# 3pinDXL-data.net
KiCad netlist of a schematic drawn in EAGLE
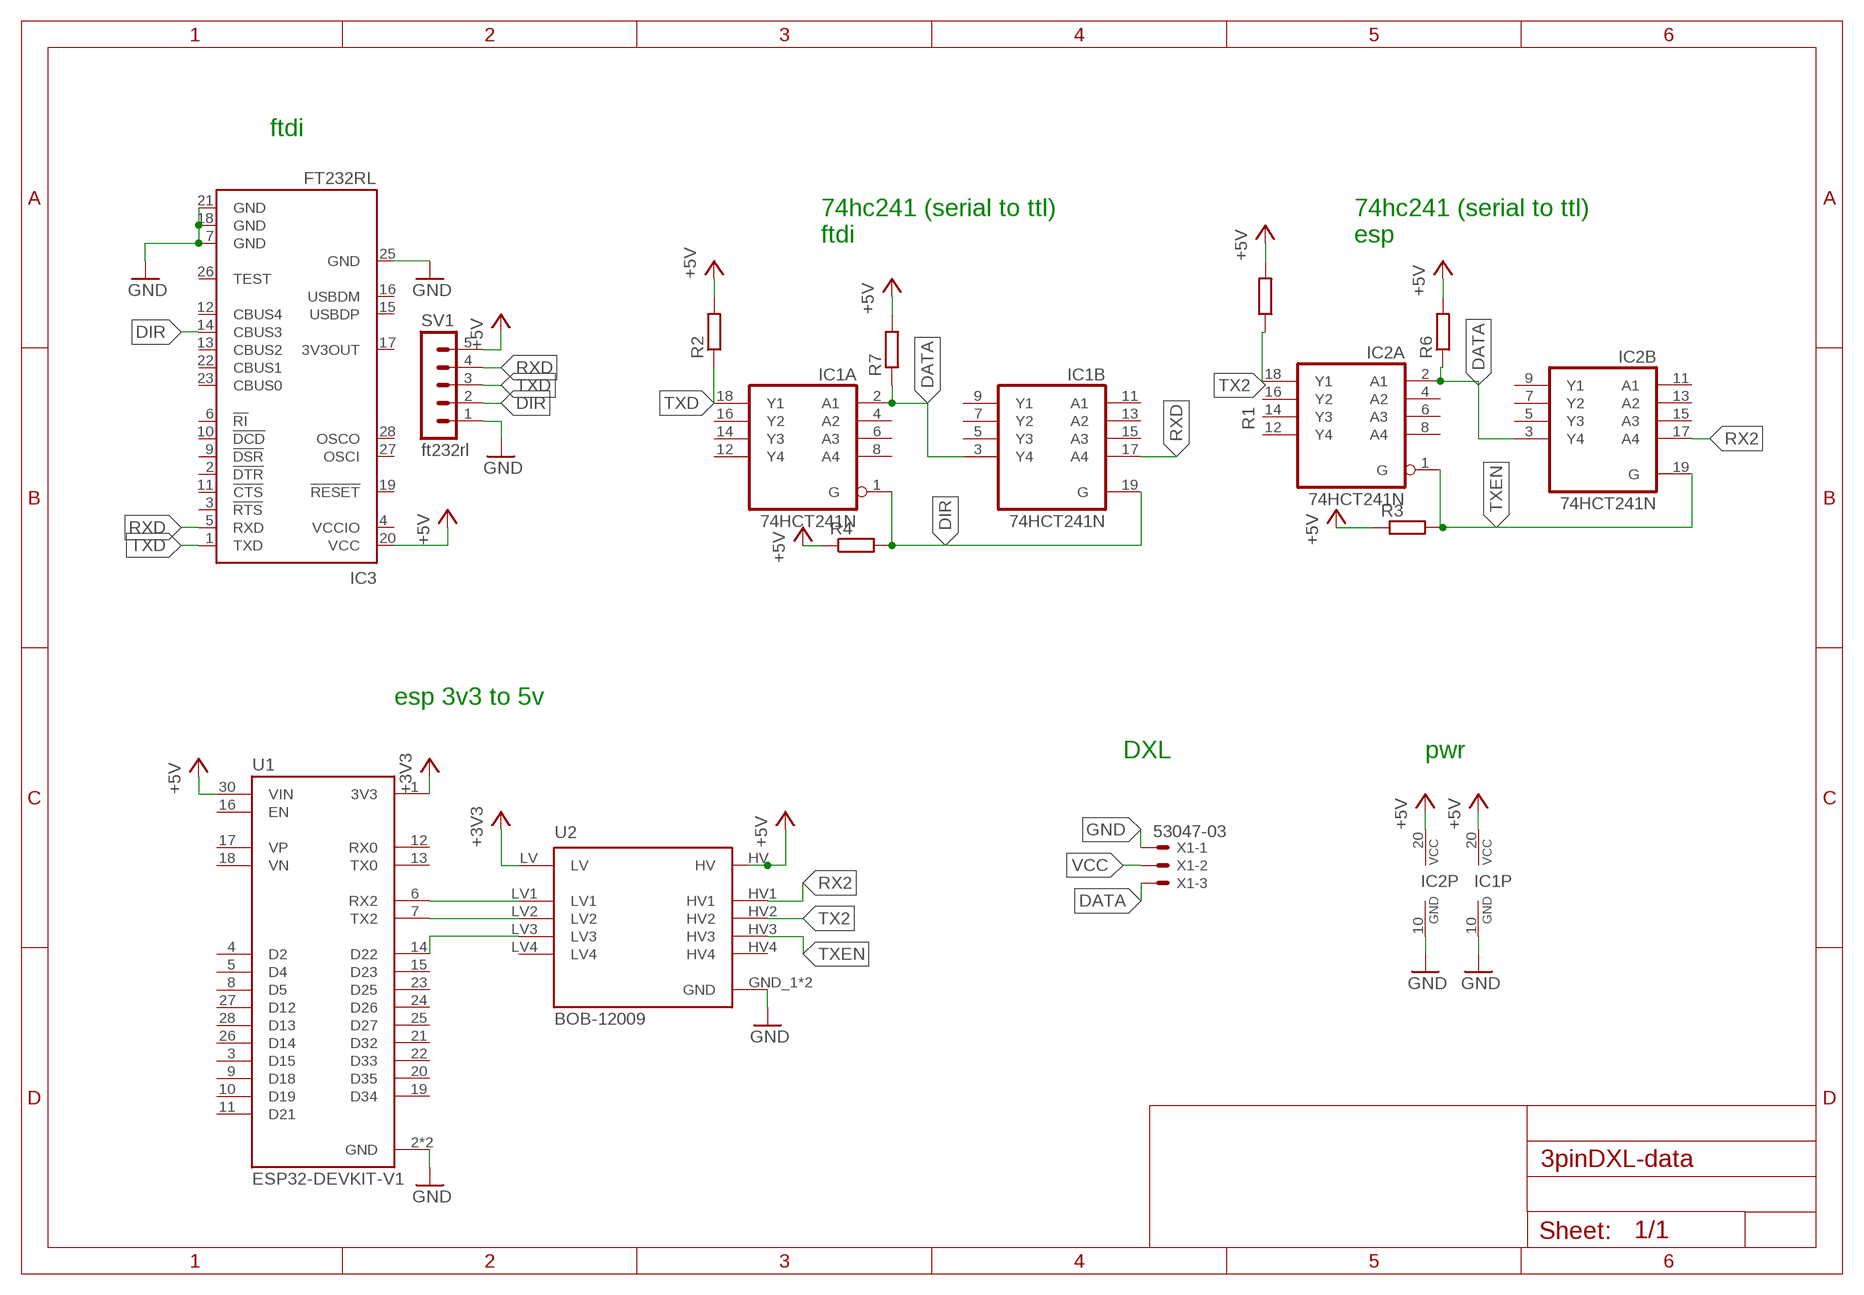
[diagram p0: schematic, sheet 1]

(export (version "E")
  (design (tool "Eeschema 10.0.6"))
  (components
    (comp (ref "IC1")
      (value "74HCT241N")
      (footprint "eagle-import:DIL20")
      (libsource (lib "eagle-import") (part "74241NHCT"))
    )
    (comp (ref "IC2")
      (value "74HCT241N")
      (footprint "eagle-import:DIL20")
      (libsource (lib "eagle-import") (part "74241NHCT"))
    )
    (comp (ref "IC3")
      (value "FT232RL")
      (footprint "eagle-import:SSOP28")
      (libsource (lib "eagle-import") (part "FT232RL"))
    )
    (comp (ref "R1")
      (value "R-EU_R0805")
      (footprint "eagle-import:R0805")
      (libsource (lib "eagle-import") (part "R-EU_R0805"))
    )
    (comp (ref "R2")
      (value "R-EU_R0805")
      (footprint "eagle-import:R0805")
      (libsource (lib "eagle-import") (part "R-EU_R0805"))
    )
    (comp (ref "R3")
      (value "R-EU_R0805")
      (footprint "eagle-import:R0805")
      (libsource (lib "eagle-import") (part "R-EU_R0805"))
    )
    (comp (ref "R4")
      (value "R-EU_R0805")
      (footprint "eagle-import:R0805")
      (libsource (lib "eagle-import") (part "R-EU_R0805"))
    )
    (comp (ref "R6")
      (value "R-EU_R0805")
      (footprint "eagle-import:R0805")
      (libsource (lib "eagle-import") (part "R-EU_R0805"))
    )
    (comp (ref "R7")
      (value "R-EU_R0805")
      (footprint "eagle-import:R0805")
      (libsource (lib "eagle-import") (part "R-EU_R0805"))
    )
    (comp (ref "SV1")
      (value "ft232rl")
      (footprint "eagle-import:MA05-1")
      (libsource (lib "eagle-import") (part "MA05-1"))
    )
    (comp (ref "U1")
      (value "ESP32-DEVKIT-V1")
      (footprint "eagle-import:MODULE_ESP32_DEVKIT_V1")
      (fields (field (name "MF") "Do it"))
      (libsource (lib "eagle-import") (part "ESP32-DEVKIT-V1"))
    )
    (comp (ref "U2")
      (value "BOB-12009")
      (footprint "eagle-import:CONV_BOB-12009")
      (fields (field (name "MF") "SparkFun"))
      (libsource (lib "eagle-import") (part "BOB-12009"))
    )
    (comp (ref "X1")
      (value "53047-03")
      (footprint "eagle-import:53047-03")
      (fields (field (name "MF") "MOLEX") (field (name "MPN") "530470310"))
      (libsource (lib "eagle-import") (part "53?-03047"))
    )
  )
  (nets
    (net (code "1") (name "+3V3") (class "Default")
      (node (ref "U1") (pin "1") (pinfunction "3V3_1") (pintype "output"))
      (node (ref "U2") (pin "LV") (pinfunction "LV_LV") (pintype "bidirectional"))
    )
    (net (code "2") (name "+5V") (class "Default")
      (node (ref "IC1") (pin "20") (pinfunction "VCC_20") (pintype "power_in"))
      (node (ref "IC2") (pin "20") (pinfunction "VCC_20") (pintype "power_in"))
      (node (ref "IC3") (pin "20") (pinfunction "VCC_20") (pintype "power_in"))
      (node (ref "R1") (pin "2") (pinfunction "2_2") (pintype "passive"))
      (node (ref "R2") (pin "2") (pinfunction "2_2") (pintype "passive"))
      (node (ref "R3") (pin "1") (pinfunction "1_1") (pintype "passive"))
      (node (ref "R4") (pin "1") (pinfunction "1_1") (pintype "passive"))
      (node (ref "R6") (pin "2") (pinfunction "2_2") (pintype "passive"))
      (node (ref "R7") (pin "2") (pinfunction "2_2") (pintype "passive"))
      (node (ref "SV1") (pin "5") (pinfunction "5_5") (pintype "passive"))
      (node (ref "U1") (pin "30") (pinfunction "VIN_30") (pintype "input"))
      (node (ref "U2") (pin "HV") (pinfunction "HV_HV") (pintype "bidirectional"))
    )
    (net (code "3") (name "/VCCIO") (class "Default")
      (node (ref "IC3") (pin "4") (pinfunction "VCCIO_4") (pintype "power_in"))
    )
    (net (code "4") (name "DATA") (class "Default")
      (node (ref "IC1") (pin "2") (pinfunction "A1_2") (pintype "input"))
      (node (ref "IC1") (pin "3") (pinfunction "Y4_3") (pintype "tri_state"))
      (node (ref "IC2") (pin "2") (pinfunction "A1_2") (pintype "input"))
      (node (ref "IC2") (pin "3") (pinfunction "Y4_3") (pintype "tri_state"))
      (node (ref "R6") (pin "1") (pinfunction "1_1") (pintype "passive"))
      (node (ref "R7") (pin "1") (pinfunction "1_1") (pintype "passive"))
      (node (ref "X1") (pin "3") (pinfunction "S_3") (pintype "passive"))
    )
    (net (code "5") (name "DIR") (class "Default")
      (node (ref "IC1") (pin "1") (pinfunction "G_1") (pintype "input"))
      (node (ref "IC1") (pin "19") (pinfunction "G_19") (pintype "input"))
      (node (ref "IC3") (pin "14") (pinfunction "CBUS3_14") (pintype "bidirectional"))
      (node (ref "R4") (pin "2") (pinfunction "2_2") (pintype "passive"))
      (node (ref "SV1") (pin "2") (pinfunction "2_2") (pintype "passive"))
    )
    (net (code "6") (name "GND") (class "Default")
      (node (ref "IC1") (pin "10") (pinfunction "GND_10") (pintype "power_in"))
      (node (ref "IC2") (pin "10") (pinfunction "GND_10") (pintype "power_in"))
      (node (ref "IC3") (pin "18") (pinfunction "GND_18") (pintype "power_in"))
      (node (ref "IC3") (pin "21") (pinfunction "GND_21") (pintype "power_in"))
      (node (ref "IC3") (pin "25") (pinfunction "GND_25") (pintype "power_in"))
      (node (ref "IC3") (pin "7") (pinfunction "GND_7") (pintype "power_in"))
      (node (ref "SV1") (pin "1") (pinfunction "1_1") (pintype "passive"))
      (node (ref "U1") (pin "2") (pinfunction "GND_2") (pintype "power_in"))
      (node (ref "U1") (pin "29") (pinfunction "GND_29") (pintype "power_in"))
      (node (ref "U2") (pin "GND_1") (pinfunction "GND_GND_1") (pintype "power_in"))
      (node (ref "U2") (pin "GND_2") (pinfunction "GND_GND_2") (pintype "power_in"))
      (node (ref "X1") (pin "1") (pinfunction "S_1") (pintype "passive"))
    )
    (net (code "7") (name "Net-(U1-D22)") (class "Default")
      (node (ref "U1") (pin "14") (pinfunction "D22_14") (pintype "bidirectional"))
      (node (ref "U2") (pin "LV3") (pinfunction "LV3_LV3") (pintype "bidirectional"))
    )
    (net (code "8") (name "Net-(U1-RX2)") (class "Default")
      (node (ref "U1") (pin "6") (pinfunction "RX2_6") (pintype "input"))
      (node (ref "U2") (pin "LV1") (pinfunction "LV1_LV1") (pintype "bidirectional"))
    )
    (net (code "9") (name "Net-(U1-TX2)") (class "Default")
      (node (ref "U1") (pin "7") (pinfunction "TX2_7") (pintype "output"))
      (node (ref "U2") (pin "LV2") (pinfunction "LV2_LV2") (pintype "bidirectional"))
    )
    (net (code "10") (name "RX2") (class "Default")
      (node (ref "IC2") (pin "17") (pinfunction "A4_17") (pintype "input"))
      (node (ref "U2") (pin "HV1") (pinfunction "HV1_HV1") (pintype "bidirectional"))
    )
    (net (code "11") (name "RXD") (class "Default")
      (node (ref "IC1") (pin "17") (pinfunction "A4_17") (pintype "input"))
      (node (ref "IC3") (pin "5") (pinfunction "RXD_5") (pintype "input"))
      (node (ref "SV1") (pin "4") (pinfunction "4_4") (pintype "passive"))
    )
    (net (code "12") (name "TX2") (class "Default")
      (node (ref "IC2") (pin "18") (pinfunction "Y1_18") (pintype "tri_state"))
      (node (ref "R1") (pin "1") (pinfunction "1_1") (pintype "passive"))
      (node (ref "U2") (pin "HV2") (pinfunction "HV2_HV2") (pintype "bidirectional"))
    )
    (net (code "13") (name "TXD") (class "Default")
      (node (ref "IC1") (pin "18") (pinfunction "Y1_18") (pintype "tri_state"))
      (node (ref "IC3") (pin "1") (pinfunction "TXD_1") (pintype "output"))
      (node (ref "R2") (pin "1") (pinfunction "1_1") (pintype "passive"))
      (node (ref "SV1") (pin "3") (pinfunction "3_3") (pintype "passive"))
    )
    (net (code "14") (name "TXEN") (class "Default")
      (node (ref "IC2") (pin "1") (pinfunction "G_1") (pintype "input"))
      (node (ref "IC2") (pin "19") (pinfunction "G_19") (pintype "input"))
      (node (ref "R3") (pin "2") (pinfunction "2_2") (pintype "passive"))
      (node (ref "U2") (pin "HV3") (pinfunction "HV3_HV3") (pintype "bidirectional"))
    )
    (net (code "15") (name "VCC") (class "Default")
      (node (ref "X1") (pin "2") (pinfunction "S_2") (pintype "passive"))
    )
    (net (code "16") (name "unconnected-(IC1A-A2-Pad4)") (class "Default")
      (node (ref "IC1") (pin "4") (pinfunction "A2_4") (pintype "input"))
    )
    (net (code "17") (name "unconnected-(IC1A-A3-Pad6)") (class "Default")
      (node (ref "IC1") (pin "6") (pinfunction "A3_6") (pintype "input"))
    )
    (net (code "18") (name "unconnected-(IC1A-A4-Pad8)") (class "Default")
      (node (ref "IC1") (pin "8") (pinfunction "A4_8") (pintype "input"))
    )
    (net (code "19") (name "unconnected-(IC1A-Y2-Pad16)") (class "Default")
      (node (ref "IC1") (pin "16") (pinfunction "Y2_16") (pintype "tri_state"))
    )
    (net (code "20") (name "unconnected-(IC1A-Y3-Pad14)") (class "Default")
      (node (ref "IC1") (pin "14") (pinfunction "Y3_14") (pintype "tri_state"))
    )
    (net (code "21") (name "unconnected-(IC1A-Y4-Pad12)") (class "Default")
      (node (ref "IC1") (pin "12") (pinfunction "Y4_12") (pintype "tri_state"))
    )
    (net (code "22") (name "unconnected-(IC1B-A1-Pad11)") (class "Default")
      (node (ref "IC1") (pin "11") (pinfunction "A1_11") (pintype "input"))
    )
    (net (code "23") (name "unconnected-(IC1B-A2-Pad13)") (class "Default")
      (node (ref "IC1") (pin "13") (pinfunction "A2_13") (pintype "input"))
    )
    (net (code "24") (name "unconnected-(IC1B-A3-Pad15)") (class "Default")
      (node (ref "IC1") (pin "15") (pinfunction "A3_15") (pintype "input"))
    )
    (net (code "25") (name "unconnected-(IC1B-Y1-Pad9)") (class "Default")
      (node (ref "IC1") (pin "9") (pinfunction "Y1_9") (pintype "tri_state"))
    )
    (net (code "26") (name "unconnected-(IC1B-Y2-Pad7)") (class "Default")
      (node (ref "IC1") (pin "7") (pinfunction "Y2_7") (pintype "tri_state"))
    )
    (net (code "27") (name "unconnected-(IC1B-Y3-Pad5)") (class "Default")
      (node (ref "IC1") (pin "5") (pinfunction "Y3_5") (pintype "tri_state"))
    )
    (net (code "28") (name "unconnected-(IC2A-A2-Pad4)") (class "Default")
      (node (ref "IC2") (pin "4") (pinfunction "A2_4") (pintype "input"))
    )
    (net (code "29") (name "unconnected-(IC2A-A3-Pad6)") (class "Default")
      (node (ref "IC2") (pin "6") (pinfunction "A3_6") (pintype "input"))
    )
    (net (code "30") (name "unconnected-(IC2A-A4-Pad8)") (class "Default")
      (node (ref "IC2") (pin "8") (pinfunction "A4_8") (pintype "input"))
    )
    (net (code "31") (name "unconnected-(IC2A-Y2-Pad16)") (class "Default")
      (node (ref "IC2") (pin "16") (pinfunction "Y2_16") (pintype "tri_state"))
    )
    (net (code "32") (name "unconnected-(IC2A-Y3-Pad14)") (class "Default")
      (node (ref "IC2") (pin "14") (pinfunction "Y3_14") (pintype "tri_state"))
    )
    (net (code "33") (name "unconnected-(IC2A-Y4-Pad12)") (class "Default")
      (node (ref "IC2") (pin "12") (pinfunction "Y4_12") (pintype "tri_state"))
    )
    (net (code "34") (name "unconnected-(IC2B-A1-Pad11)") (class "Default")
      (node (ref "IC2") (pin "11") (pinfunction "A1_11") (pintype "input"))
    )
    (net (code "35") (name "unconnected-(IC2B-A2-Pad13)") (class "Default")
      (node (ref "IC2") (pin "13") (pinfunction "A2_13") (pintype "input"))
    )
    (net (code "36") (name "unconnected-(IC2B-A3-Pad15)") (class "Default")
      (node (ref "IC2") (pin "15") (pinfunction "A3_15") (pintype "input"))
    )
    (net (code "37") (name "unconnected-(IC2B-Y1-Pad9)") (class "Default")
      (node (ref "IC2") (pin "9") (pinfunction "Y1_9") (pintype "tri_state"))
    )
    (net (code "38") (name "unconnected-(IC2B-Y2-Pad7)") (class "Default")
      (node (ref "IC2") (pin "7") (pinfunction "Y2_7") (pintype "tri_state"))
    )
    (net (code "39") (name "unconnected-(IC2B-Y3-Pad5)") (class "Default")
      (node (ref "IC2") (pin "5") (pinfunction "Y3_5") (pintype "tri_state"))
    )
    (net (code "40") (name "unconnected-(IC3-3V3OUT-Pad17)") (class "Default")
      (node (ref "IC3") (pin "17") (pinfunction "3V3OUT_17") (pintype "output"))
    )
    (net (code "41") (name "unconnected-(IC3-CBUS0-Pad23)") (class "Default")
      (node (ref "IC3") (pin "23") (pinfunction "CBUS0_23") (pintype "bidirectional"))
    )
    (net (code "42") (name "unconnected-(IC3-CBUS1-Pad22)") (class "Default")
      (node (ref "IC3") (pin "22") (pinfunction "CBUS1_22") (pintype "bidirectional"))
    )
    (net (code "43") (name "unconnected-(IC3-CBUS2-Pad13)") (class "Default")
      (node (ref "IC3") (pin "13") (pinfunction "CBUS2_13") (pintype "bidirectional"))
    )
    (net (code "44") (name "unconnected-(IC3-CBUS4-Pad12)") (class "Default")
      (node (ref "IC3") (pin "12") (pinfunction "CBUS4_12") (pintype "bidirectional"))
    )
    (net (code "45") (name "unconnected-(IC3-OSCI-Pad27)") (class "Default")
      (node (ref "IC3") (pin "27") (pinfunction "OSCI_27") (pintype "input"))
    )
    (net (code "46") (name "unconnected-(IC3-OSCO-Pad28)") (class "Default")
      (node (ref "IC3") (pin "28") (pinfunction "OSCO_28") (pintype "output"))
    )
    (net (code "47") (name "unconnected-(IC3-TEST-Pad26)") (class "Default")
      (node (ref "IC3") (pin "26") (pinfunction "TEST_26") (pintype "input"))
    )
    (net (code "48") (name "unconnected-(IC3-USBDM-Pad16)") (class "Default")
      (node (ref "IC3") (pin "16") (pinfunction "USBDM_16") (pintype "bidirectional"))
    )
    (net (code "49") (name "unconnected-(IC3-USBDP-Pad15)") (class "Default")
      (node (ref "IC3") (pin "15") (pinfunction "USBDP_15") (pintype "bidirectional"))
    )
    (net (code "50") (name "unconnected-(IC3-~{CTS}-Pad11)") (class "Default")
      (node (ref "IC3") (pin "11") (pinfunction "~{CTS}_11") (pintype "input"))
    )
    (net (code "51") (name "unconnected-(IC3-~{DCD}-Pad10)") (class "Default")
      (node (ref "IC3") (pin "10") (pinfunction "~{DCD}_10") (pintype "input"))
    )
    (net (code "52") (name "unconnected-(IC3-~{DSR}-Pad9)") (class "Default")
      (node (ref "IC3") (pin "9") (pinfunction "~{DSR}_9") (pintype "input"))
    )
    (net (code "53") (name "unconnected-(IC3-~{DTR}-Pad2)") (class "Default")
      (node (ref "IC3") (pin "2") (pinfunction "~{DTR}_2") (pintype "output"))
    )
    (net (code "54") (name "unconnected-(IC3-~{RESET}-Pad19)") (class "Default")
      (node (ref "IC3") (pin "19") (pinfunction "~{RESET}_19") (pintype "input"))
    )
    (net (code "55") (name "unconnected-(IC3-~{RI}-Pad6)") (class "Default")
      (node (ref "IC3") (pin "6") (pinfunction "~{RI}_6") (pintype "input"))
    )
    (net (code "56") (name "unconnected-(IC3-~{RTS}-Pad3)") (class "Default")
      (node (ref "IC3") (pin "3") (pinfunction "~{RTS}_3") (pintype "output"))
    )
    (net (code "57") (name "unconnected-(U1-D2-Pad4)") (class "Default")
      (node (ref "U1") (pin "4") (pinfunction "D2_4") (pintype "bidirectional"))
    )
    (net (code "58") (name "unconnected-(U1-D4-Pad5)") (class "Default")
      (node (ref "U1") (pin "5") (pinfunction "D4_5") (pintype "bidirectional"))
    )
    (net (code "59") (name "unconnected-(U1-D5-Pad8)") (class "Default")
      (node (ref "U1") (pin "8") (pinfunction "D5_8") (pintype "bidirectional"))
    )
    (net (code "60") (name "unconnected-(U1-D12-Pad27)") (class "Default")
      (node (ref "U1") (pin "27") (pinfunction "D12_27") (pintype "bidirectional"))
    )
    (net (code "61") (name "unconnected-(U1-D13-Pad28)") (class "Default")
      (node (ref "U1") (pin "28") (pinfunction "D13_28") (pintype "bidirectional"))
    )
    (net (code "62") (name "unconnected-(U1-D14-Pad26)") (class "Default")
      (node (ref "U1") (pin "26") (pinfunction "D14_26") (pintype "bidirectional"))
    )
    (net (code "63") (name "unconnected-(U1-D15-Pad3)") (class "Default")
      (node (ref "U1") (pin "3") (pinfunction "D15_3") (pintype "bidirectional"))
    )
    (net (code "64") (name "unconnected-(U1-D18-Pad9)") (class "Default")
      (node (ref "U1") (pin "9") (pinfunction "D18_9") (pintype "bidirectional"))
    )
    (net (code "65") (name "unconnected-(U1-D19-Pad10)") (class "Default")
      (node (ref "U1") (pin "10") (pinfunction "D19_10") (pintype "bidirectional"))
    )
    (net (code "66") (name "unconnected-(U1-D21-Pad11)") (class "Default")
      (node (ref "U1") (pin "11") (pinfunction "D21_11") (pintype "bidirectional"))
    )
    (net (code "67") (name "unconnected-(U1-D23-Pad15)") (class "Default")
      (node (ref "U1") (pin "15") (pinfunction "D23_15") (pintype "bidirectional"))
    )
    (net (code "68") (name "unconnected-(U1-D25-Pad23)") (class "Default")
      (node (ref "U1") (pin "23") (pinfunction "D25_23") (pintype "bidirectional"))
    )
    (net (code "69") (name "unconnected-(U1-D26-Pad24)") (class "Default")
      (node (ref "U1") (pin "24") (pinfunction "D26_24") (pintype "bidirectional"))
    )
    (net (code "70") (name "unconnected-(U1-D27-Pad25)") (class "Default")
      (node (ref "U1") (pin "25") (pinfunction "D27_25") (pintype "bidirectional"))
    )
    (net (code "71") (name "unconnected-(U1-D32-Pad21)") (class "Default")
      (node (ref "U1") (pin "21") (pinfunction "D32_21") (pintype "bidirectional"))
    )
    (net (code "72") (name "unconnected-(U1-D33-Pad22)") (class "Default")
      (node (ref "U1") (pin "22") (pinfunction "D33_22") (pintype "bidirectional"))
    )
    (net (code "73") (name "unconnected-(U1-D34-Pad19)") (class "Default")
      (node (ref "U1") (pin "19") (pinfunction "D34_19") (pintype "bidirectional"))
    )
    (net (code "74") (name "unconnected-(U1-D35-Pad20)") (class "Default")
      (node (ref "U1") (pin "20") (pinfunction "D35_20") (pintype "bidirectional"))
    )
    (net (code "75") (name "unconnected-(U1-EN-Pad16)") (class "Default")
      (node (ref "U1") (pin "16") (pinfunction "EN_16") (pintype "input"))
    )
    (net (code "76") (name "unconnected-(U1-RX0-Pad12)") (class "Default")
      (node (ref "U1") (pin "12") (pinfunction "RX0_12") (pintype "input"))
    )
    (net (code "77") (name "unconnected-(U1-TX0-Pad13)") (class "Default")
      (node (ref "U1") (pin "13") (pinfunction "TX0_13") (pintype "output"))
    )
    (net (code "78") (name "unconnected-(U1-VN-Pad18)") (class "Default")
      (node (ref "U1") (pin "18") (pinfunction "VN_18") (pintype "bidirectional"))
    )
    (net (code "79") (name "unconnected-(U1-VP-Pad17)") (class "Default")
      (node (ref "U1") (pin "17") (pinfunction "VP_17") (pintype "bidirectional"))
    )
    (net (code "80") (name "unconnected-(U2-PadHV4)") (class "Default")
      (node (ref "U2") (pin "HV4") (pinfunction "HV4_HV4") (pintype "bidirectional"))
    )
    (net (code "81") (name "unconnected-(U2-PadLV4)") (class "Default")
      (node (ref "U2") (pin "LV4") (pinfunction "LV4_LV4") (pintype "bidirectional"))
    )
  )
)
